# ledhub_r3.net
KiCad netlist of a schematic drawn in EAGLE
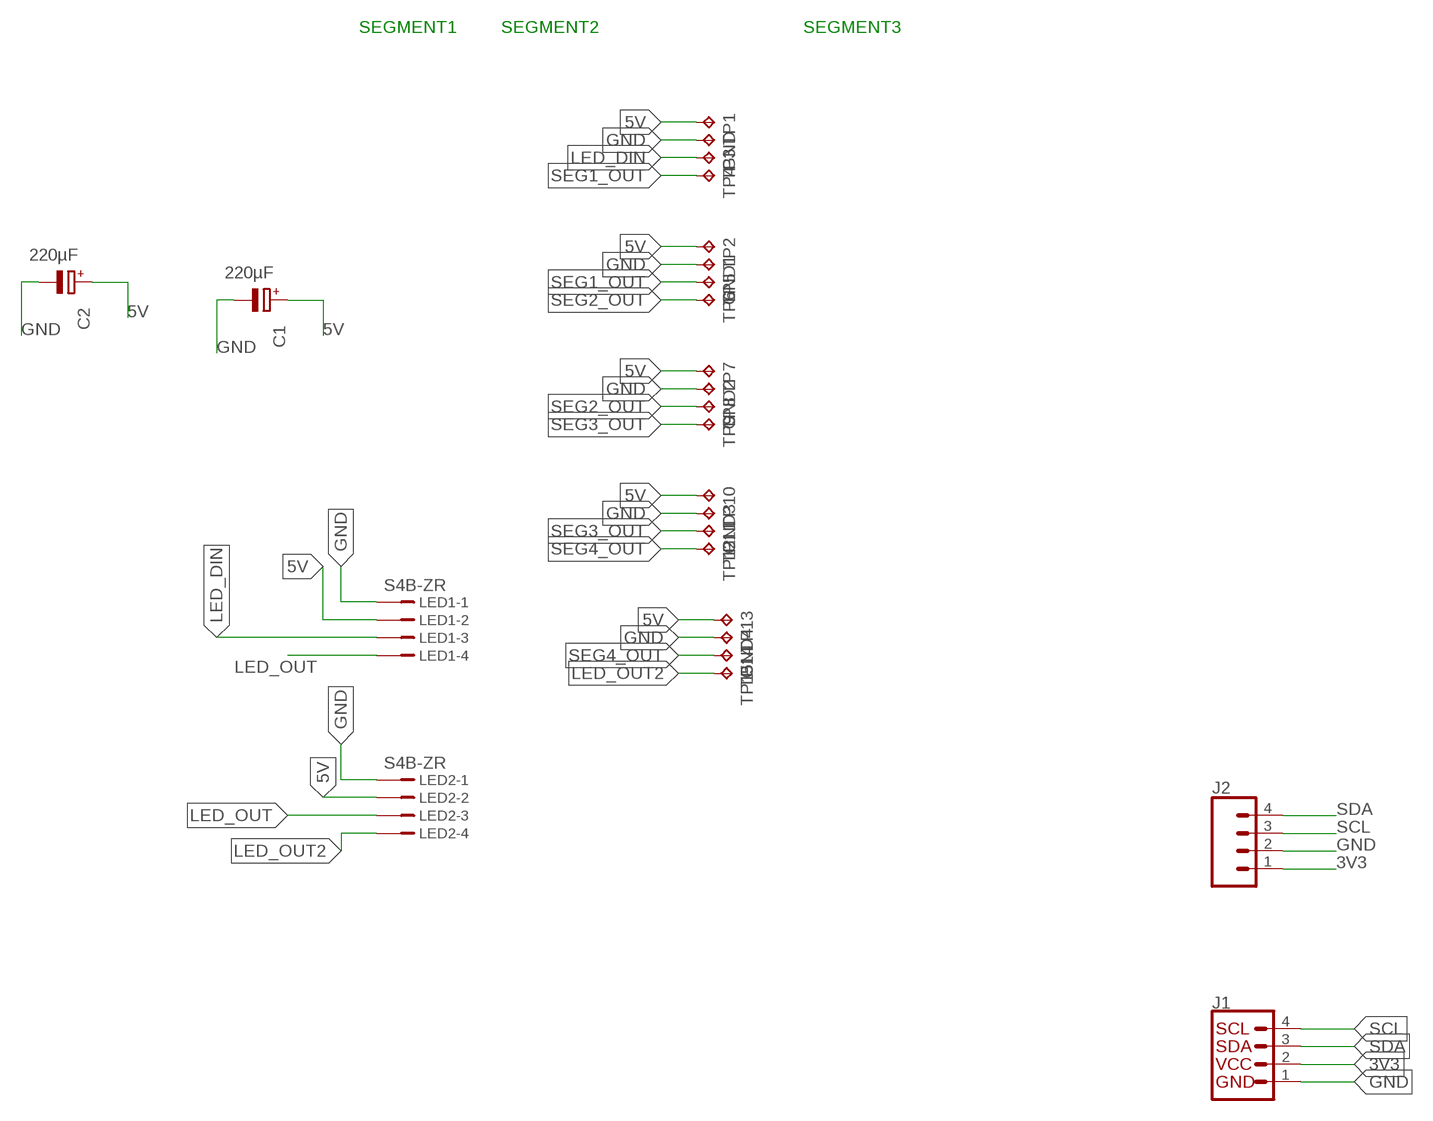
[diagram p0: schematic, sheet 1]

(export (version "E")
  (design (tool "Eeschema 10.0.6"))
  (components
    (comp (ref "C1")
      (value "220µF")
      (footprint "eagle-import:PANASONIC_D")
      (libsource (lib "eagle-import") (part "CPOL-EUD"))
    )
    (comp (ref "C2")
      (value "220µF")
      (footprint "eagle-import:PANASONIC_D")
      (libsource (lib "eagle-import") (part "CPOL-EUD"))
    )
    (comp (ref "GND")
      (value "TPTP15SQ")
      (footprint "eagle-import:TP15SQ")
      (libsource (lib "eagle-import") (part "TPTP15SQ"))
    )
    (comp (ref "GND1")
      (value "TPTP15SQ")
      (footprint "eagle-import:TP15SQ")
      (libsource (lib "eagle-import") (part "TPTP15SQ"))
    )
    (comp (ref "GND2")
      (value "TPTP15SQ")
      (footprint "eagle-import:TP15SQ")
      (libsource (lib "eagle-import") (part "TPTP15SQ"))
    )
    (comp (ref "GND3")
      (value "TPTP15SQ")
      (footprint "eagle-import:TP15SQ")
      (libsource (lib "eagle-import") (part "TPTP15SQ"))
    )
    (comp (ref "GND4")
      (value "TPTP15SQ")
      (footprint "eagle-import:TP15SQ")
      (libsource (lib "eagle-import") (part "TPTP15SQ"))
    )
    (comp (ref "J1")
      (value "QWIIC_CONNECTORJS-1MM")
      (footprint "eagle-import:1X04_1MM_RA")
      (libsource (lib "eagle-import") (part "QWIIC_CONNECTORJS-1MM"))
    )
    (comp (ref "J2")
      (value "CONN_04")
      (footprint "eagle-import:1X04")
      (libsource (lib "eagle-import") (part "CONN_04"))
    )
    (comp (ref "LED1")
      (value "S4B-ZR")
      (footprint "eagle-import:S4B-ZR")
      (fields (field (name "MF") "FARNELL") (field (name "MPN") "S4B-ZR(LF)(SN)"))
      (libsource (lib "eagle-import") (part "?4B-ZRS"))
    )
    (comp (ref "LED2")
      (value "S4B-ZR")
      (footprint "eagle-import:S4B-ZR")
      (fields (field (name "MF") "FARNELL") (field (name "MPN") "S4B-ZR(LF)(SN)"))
      (libsource (lib "eagle-import") (part "?4B-ZRS"))
    )
    (comp (ref "TP1")
      (value "TPTP15R")
      (footprint "eagle-import:TP15R")
      (libsource (lib "eagle-import") (part "TPTP15R"))
    )
    (comp (ref "TP2")
      (value "TPTP15R")
      (footprint "eagle-import:TP15R")
      (libsource (lib "eagle-import") (part "TPTP15R"))
    )
    (comp (ref "TP3")
      (value "TPTP15R")
      (footprint "eagle-import:TP15R")
      (libsource (lib "eagle-import") (part "TPTP15R"))
    )
    (comp (ref "TP4")
      (value "TPTP15R")
      (footprint "eagle-import:TP15R")
      (libsource (lib "eagle-import") (part "TPTP15R"))
    )
    (comp (ref "TP5")
      (value "TPTP15R")
      (footprint "eagle-import:TP15R")
      (libsource (lib "eagle-import") (part "TPTP15R"))
    )
    (comp (ref "TP6")
      (value "TPTP15R")
      (footprint "eagle-import:TP15R")
      (libsource (lib "eagle-import") (part "TPTP15R"))
    )
    (comp (ref "TP7")
      (value "TPTP15R")
      (footprint "eagle-import:TP15R")
      (libsource (lib "eagle-import") (part "TPTP15R"))
    )
    (comp (ref "TP8")
      (value "TPTP15R")
      (footprint "eagle-import:TP15R")
      (libsource (lib "eagle-import") (part "TPTP15R"))
    )
    (comp (ref "TP9")
      (value "TPTP15R")
      (footprint "eagle-import:TP15R")
      (libsource (lib "eagle-import") (part "TPTP15R"))
    )
    (comp (ref "TP10")
      (value "TPTP15R")
      (footprint "eagle-import:TP15R")
      (libsource (lib "eagle-import") (part "TPTP15R"))
    )
    (comp (ref "TP11")
      (value "TPTP15R")
      (footprint "eagle-import:TP15R")
      (libsource (lib "eagle-import") (part "TPTP15R"))
    )
    (comp (ref "TP12")
      (value "TPTP15R")
      (footprint "eagle-import:TP15R")
      (libsource (lib "eagle-import") (part "TPTP15R"))
    )
    (comp (ref "TP13")
      (value "TPTP15R")
      (footprint "eagle-import:TP15R")
      (libsource (lib "eagle-import") (part "TPTP15R"))
    )
    (comp (ref "TP14")
      (value "TPTP15R")
      (footprint "eagle-import:TP15R")
      (libsource (lib "eagle-import") (part "TPTP15R"))
    )
    (comp (ref "TP15")
      (value "TPTP15R")
      (footprint "eagle-import:TP15R")
      (libsource (lib "eagle-import") (part "TPTP15R"))
    )
  )
  (nets
    (net (code "1") (name "3V3") (class "Default")
      (node (ref "J1") (pin "2") (pinfunction "VCC_2") (pintype "power_in"))
      (node (ref "J2") (pin "1") (pinfunction "1_1") (pintype "passive"))
    )
    (net (code "2") (name "5V") (class "Default")
      (node (ref "C1") (pin "+") (pinfunction "+_+") (pintype "passive"))
      (node (ref "C2") (pin "+") (pinfunction "+_+") (pintype "passive"))
      (node (ref "LED1") (pin "2") (pinfunction "1_2") (pintype "passive"))
      (node (ref "LED2") (pin "2") (pinfunction "1_2") (pintype "passive"))
      (node (ref "TP1") (pin "TP") (pinfunction "TP_TP") (pintype "input"))
      (node (ref "TP10") (pin "TP") (pinfunction "TP_TP") (pintype "input"))
      (node (ref "TP13") (pin "TP") (pinfunction "TP_TP") (pintype "input"))
      (node (ref "TP2") (pin "TP") (pinfunction "TP_TP") (pintype "input"))
      (node (ref "TP7") (pin "TP") (pinfunction "TP_TP") (pintype "input"))
    )
    (net (code "3") (name "GND") (class "Default")
      (node (ref "C1") (pin "-") (pinfunction "-_-") (pintype "passive"))
      (node (ref "C2") (pin "-") (pinfunction "-_-") (pintype "passive"))
      (node (ref "GND") (pin "TP") (pinfunction "TP_TP") (pintype "input"))
      (node (ref "GND1") (pin "TP") (pinfunction "TP_TP") (pintype "input"))
      (node (ref "GND2") (pin "TP") (pinfunction "TP_TP") (pintype "input"))
      (node (ref "GND3") (pin "TP") (pinfunction "TP_TP") (pintype "input"))
      (node (ref "GND4") (pin "TP") (pinfunction "TP_TP") (pintype "input"))
      (node (ref "J1") (pin "1") (pinfunction "GND_1") (pintype "power_in"))
      (node (ref "J2") (pin "2") (pinfunction "2_2") (pintype "passive"))
      (node (ref "LED1") (pin "1") (pinfunction "1_1") (pintype "passive"))
      (node (ref "LED2") (pin "1") (pinfunction "1_1") (pintype "passive"))
    )
    (net (code "4") (name "LED_DIN") (class "Default")
      (node (ref "LED1") (pin "3") (pinfunction "1_3") (pintype "passive"))
      (node (ref "TP3") (pin "TP") (pinfunction "TP_TP") (pintype "input"))
    )
    (net (code "5") (name "LED_OUT") (class "Default")
      (node (ref "LED1") (pin "4") (pinfunction "1_4") (pintype "passive"))
      (node (ref "LED2") (pin "3") (pinfunction "1_3") (pintype "passive"))
    )
    (net (code "6") (name "LED_OUT2") (class "Default")
      (node (ref "LED2") (pin "4") (pinfunction "1_4") (pintype "passive"))
      (node (ref "TP15") (pin "TP") (pinfunction "TP_TP") (pintype "input"))
    )
    (net (code "7") (name "SCL") (class "Default")
      (node (ref "J1") (pin "4") (pinfunction "SCL_4") (pintype "passive"))
      (node (ref "J2") (pin "3") (pinfunction "3_3") (pintype "passive"))
    )
    (net (code "8") (name "SDA") (class "Default")
      (node (ref "J1") (pin "3") (pinfunction "SDA_3") (pintype "passive"))
      (node (ref "J2") (pin "4") (pinfunction "4_4") (pintype "passive"))
    )
    (net (code "9") (name "SEG1_OUT") (class "Default")
      (node (ref "TP4") (pin "TP") (pinfunction "TP_TP") (pintype "input"))
      (node (ref "TP5") (pin "TP") (pinfunction "TP_TP") (pintype "input"))
    )
    (net (code "10") (name "SEG2_OUT") (class "Default")
      (node (ref "TP6") (pin "TP") (pinfunction "TP_TP") (pintype "input"))
      (node (ref "TP8") (pin "TP") (pinfunction "TP_TP") (pintype "input"))
    )
    (net (code "11") (name "SEG3_OUT") (class "Default")
      (node (ref "TP11") (pin "TP") (pinfunction "TP_TP") (pintype "input"))
      (node (ref "TP9") (pin "TP") (pinfunction "TP_TP") (pintype "input"))
    )
    (net (code "12") (name "SEG4_OUT") (class "Default")
      (node (ref "TP12") (pin "TP") (pinfunction "TP_TP") (pintype "input"))
      (node (ref "TP14") (pin "TP") (pinfunction "TP_TP") (pintype "input"))
    )
  )
)
